# BSB-Board.net
KiCad netlist of a schematic drawn in EAGLE
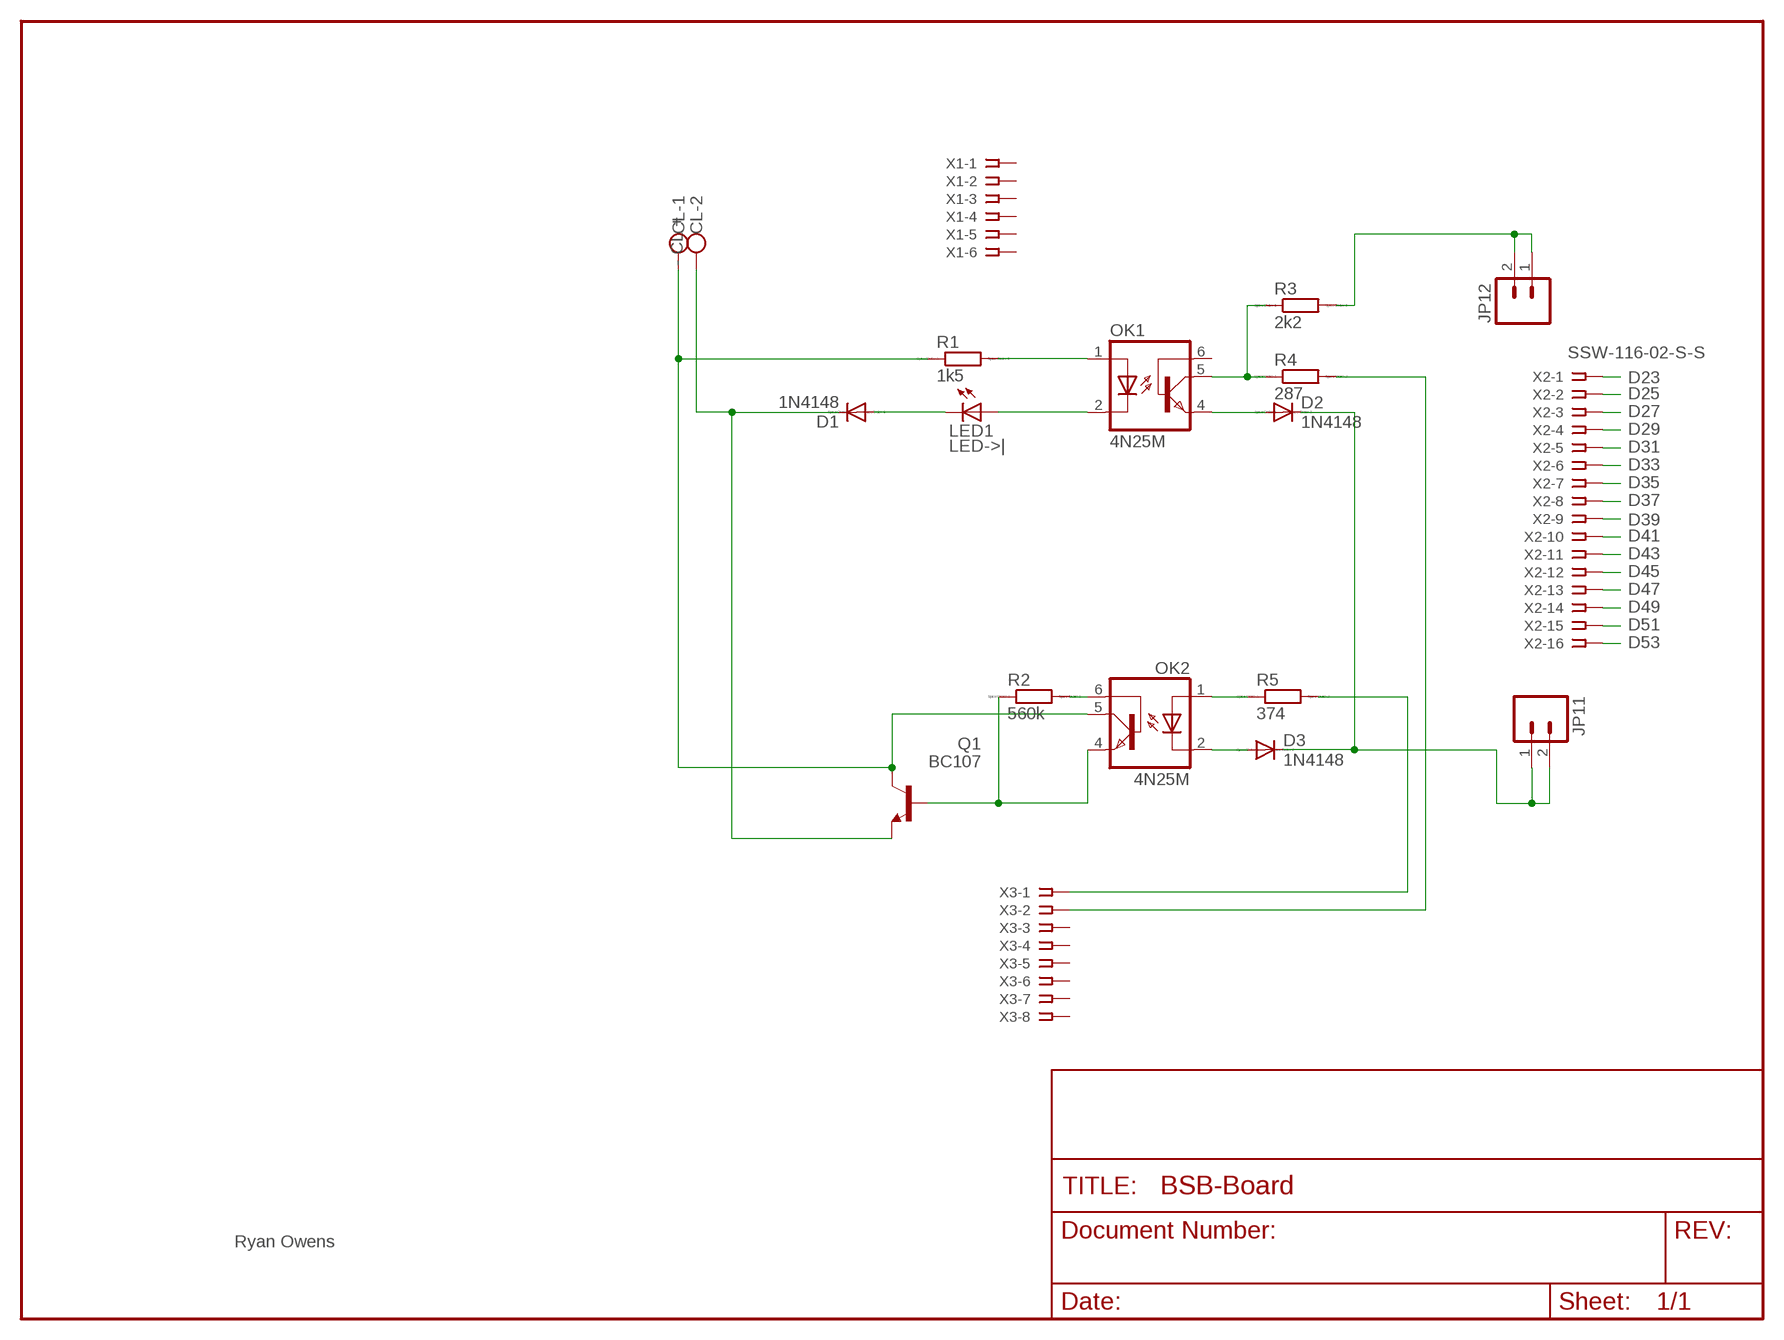
[diagram p0: schematic, sheet 1]

(export (version "E")
  (design (tool "Eeschema 10.0.6"))
  (components
    (comp (ref "CL")
      (value "- CL +")
      (footprint "eagle-import:W237-102")
      (fields (field (name "MPN") "237-102"))
      (libsource (lib "eagle-import") (part "W237-102"))
    )
    (comp (ref "D1")
      (value "1N4148")
      (footprint "eagle-import:DO35-7")
      (libsource (lib "eagle-import") (part "1N4148DO35-7"))
    )
    (comp (ref "D2")
      (value "1N4148")
      (footprint "eagle-import:DO35-7")
      (libsource (lib "eagle-import") (part "1N4148DO35-7"))
    )
    (comp (ref "D3")
      (value "1N4148")
      (footprint "eagle-import:DO35-7")
      (libsource (lib "eagle-import") (part "1N4148DO35-7"))
    )
    (comp (ref "JP11")
      (value "M02LOCK")
      (footprint "eagle-import:1X02_LOCK")
      (libsource (lib "eagle-import") (part "M02LOCK"))
    )
    (comp (ref "JP12")
      (value "M02LOCK")
      (footprint "eagle-import:1X02_LOCK")
      (libsource (lib "eagle-import") (part "M02LOCK"))
    )
    (comp (ref "LED1")
      (value "LED->|")
      (footprint "eagle-import:LED2X5")
      (libsource (lib "eagle-import") (part "LEDSQR2X5"))
    )
    (comp (ref "OK1")
      (value "4N25M")
      (footprint "eagle-import:DIL06")
      (fields (field (name "MPN") "4N25-M"))
      (libsource (lib "eagle-import") (part "4N?M25"))
    )
    (comp (ref "OK2")
      (value "4N25M")
      (footprint "eagle-import:DIL06")
      (fields (field (name "MPN") "4N25-M"))
      (libsource (lib "eagle-import") (part "4N?M25"))
    )
    (comp (ref "Q1")
      (value "BC107")
      (footprint "eagle-import:TO18")
      (libsource (lib "eagle-import") (part "BC107"))
    )
    (comp (ref "R1")
      (value "1k5")
      (footprint "eagle-import:0204_7")
      (libsource (lib "eagle-import") (part "R0204/7"))
    )
    (comp (ref "R2")
      (value "560k")
      (footprint "eagle-import:0207_10")
      (libsource (lib "eagle-import") (part "R0207/10"))
    )
    (comp (ref "R3")
      (value "2k2")
      (footprint "eagle-import:0204_7")
      (libsource (lib "eagle-import") (part "R0204/7"))
    )
    (comp (ref "R4")
      (value "287")
      (footprint "eagle-import:0204_7")
      (libsource (lib "eagle-import") (part "R0204/7"))
    )
    (comp (ref "R5")
      (value "374")
      (footprint "eagle-import:0204_7")
      (libsource (lib "eagle-import") (part "R0204/7"))
    )
    (comp (ref "X1")
      (value "SSW-106-02-S-S")
      (footprint "eagle-import:SSW-106-02-S-S")
      (libsource (lib "eagle-import") (part "SSW-106-02-S-S"))
    )
    (comp (ref "X2")
      (value "SSW-116-02-S-S")
      (footprint "eagle-import:SSW-116-02-S-S")
      (libsource (lib "eagle-import") (part "SSW-116-02-S-S"))
    )
    (comp (ref "X3")
      (value "SSW-108-02-S-S")
      (footprint "eagle-import:SSW-108-02-S-S")
      (libsource (lib "eagle-import") (part "SSW-108-02-S-S"))
    )
  )
  (nets
    (net (code "1") (name "/D23") (class "Default")
      (node (ref "X2") (pin "1") (pinfunction "1_1") (pintype "passive"))
    )
    (net (code "2") (name "/D25") (class "Default")
      (node (ref "X2") (pin "2") (pinfunction "1_2") (pintype "passive"))
    )
    (net (code "3") (name "/D27") (class "Default")
      (node (ref "X2") (pin "3") (pinfunction "1_3") (pintype "passive"))
    )
    (net (code "4") (name "/D29") (class "Default")
      (node (ref "X2") (pin "4") (pinfunction "1_4") (pintype "passive"))
    )
    (net (code "5") (name "/D31") (class "Default")
      (node (ref "X2") (pin "5") (pinfunction "1_5") (pintype "passive"))
    )
    (net (code "6") (name "/D33") (class "Default")
      (node (ref "X2") (pin "6") (pinfunction "1_6") (pintype "passive"))
    )
    (net (code "7") (name "/D35") (class "Default")
      (node (ref "X2") (pin "7") (pinfunction "1_7") (pintype "passive"))
    )
    (net (code "8") (name "/D37") (class "Default")
      (node (ref "X2") (pin "8") (pinfunction "1_8") (pintype "passive"))
    )
    (net (code "9") (name "/D39") (class "Default")
      (node (ref "X2") (pin "9") (pinfunction "1_9") (pintype "passive"))
    )
    (net (code "10") (name "/D41") (class "Default")
      (node (ref "X2") (pin "10") (pinfunction "1_10") (pintype "passive"))
    )
    (net (code "11") (name "/D43") (class "Default")
      (node (ref "X2") (pin "11") (pinfunction "1_11") (pintype "passive"))
    )
    (net (code "12") (name "/D45") (class "Default")
      (node (ref "X2") (pin "12") (pinfunction "1_12") (pintype "passive"))
    )
    (net (code "13") (name "/D47") (class "Default")
      (node (ref "X2") (pin "13") (pinfunction "1_13") (pintype "passive"))
    )
    (net (code "14") (name "/D49") (class "Default")
      (node (ref "X2") (pin "14") (pinfunction "1_14") (pintype "passive"))
    )
    (net (code "15") (name "/D51") (class "Default")
      (node (ref "X2") (pin "15") (pinfunction "1_15") (pintype "passive"))
    )
    (net (code "16") (name "/D53") (class "Default")
      (node (ref "X2") (pin "16") (pinfunction "1_16") (pintype "passive"))
    )
    (net (code "17") (name "Net-(CLA-KL)") (class "Default")
      (node (ref "CL") (pin "1") (pinfunction "KL_1") (pintype "passive"))
      (node (ref "OK2") (pin "5") (pinfunction "COL_5") (pintype "passive"))
      (node (ref "Q1") (pin "3") (pinfunction "C_3") (pintype "passive"))
      (node (ref "R1") (pin "1") (pinfunction "1_1") (pintype "passive"))
    )
    (net (code "18") (name "Net-(CLB-KL)") (class "Default")
      (node (ref "CL") (pin "2") (pinfunction "KL_2") (pintype "passive"))
      (node (ref "D1") (pin "C") (pinfunction "C_C") (pintype "passive"))
      (node (ref "Q1") (pin "1") (pinfunction "E_1") (pintype "passive"))
    )
    (net (code "19") (name "Net-(D2-PadC)") (class "Default")
      (node (ref "D2") (pin "C") (pinfunction "C_C") (pintype "passive"))
      (node (ref "D3") (pin "C") (pinfunction "C_C") (pintype "passive"))
      (node (ref "JP11") (pin "1") (pinfunction "1_1") (pintype "passive"))
      (node (ref "JP11") (pin "2") (pinfunction "2_2") (pintype "passive"))
    )
    (net (code "20") (name "Net-(JP12-Pad1)") (class "Default")
      (node (ref "JP12") (pin "1") (pinfunction "1_1") (pintype "passive"))
      (node (ref "JP12") (pin "2") (pinfunction "2_2") (pintype "passive"))
      (node (ref "R3") (pin "2") (pinfunction "2_2") (pintype "passive"))
    )
    (net (code "21") (name "Net-(LED1-C)") (class "Default")
      (node (ref "D1") (pin "A") (pinfunction "A_A") (pintype "passive"))
      (node (ref "LED1") (pin "K") (pinfunction "C_K") (pintype "passive"))
    )
    (net (code "22") (name "Net-(OK1-A)") (class "Default")
      (node (ref "OK1") (pin "1") (pinfunction "A_1") (pintype "passive"))
      (node (ref "R1") (pin "2") (pinfunction "2_2") (pintype "passive"))
    )
    (net (code "23") (name "Net-(OK1-C)") (class "Default")
      (node (ref "LED1") (pin "A") (pinfunction "A_A") (pintype "passive"))
      (node (ref "OK1") (pin "2") (pinfunction "C_2") (pintype "passive"))
    )
    (net (code "24") (name "Net-(OK1-COL)") (class "Default")
      (node (ref "OK1") (pin "5") (pinfunction "COL_5") (pintype "passive"))
      (node (ref "R3") (pin "1") (pinfunction "1_1") (pintype "passive"))
      (node (ref "R4") (pin "1") (pinfunction "1_1") (pintype "passive"))
    )
    (net (code "25") (name "Net-(OK1-EMI)") (class "Default")
      (node (ref "D2") (pin "A") (pinfunction "A_A") (pintype "passive"))
      (node (ref "OK1") (pin "4") (pinfunction "EMI_4") (pintype "passive"))
    )
    (net (code "26") (name "Net-(OK2-A)") (class "Default")
      (node (ref "OK2") (pin "1") (pinfunction "A_1") (pintype "passive"))
      (node (ref "R5") (pin "1") (pinfunction "1_1") (pintype "passive"))
    )
    (net (code "27") (name "Net-(OK2-BAS)") (class "Default")
      (node (ref "OK2") (pin "6") (pinfunction "BAS_6") (pintype "passive"))
      (node (ref "R2") (pin "2") (pinfunction "2_2") (pintype "passive"))
    )
    (net (code "28") (name "Net-(OK2-C)") (class "Default")
      (node (ref "D3") (pin "A") (pinfunction "A_A") (pintype "passive"))
      (node (ref "OK2") (pin "2") (pinfunction "C_2") (pintype "passive"))
    )
    (net (code "29") (name "Net-(OK2-EMI)") (class "Default")
      (node (ref "OK2") (pin "4") (pinfunction "EMI_4") (pintype "passive"))
      (node (ref "Q1") (pin "2") (pinfunction "B_2") (pintype "passive"))
      (node (ref "R2") (pin "1") (pinfunction "1_1") (pintype "passive"))
    )
    (net (code "30") (name "Net-(R5-Pad2)") (class "Default")
      (node (ref "R5") (pin "2") (pinfunction "2_2") (pintype "passive"))
      (node (ref "X3") (pin "1") (pinfunction "1_1") (pintype "passive"))
    )
    (net (code "31") (name "Net-(X3B-1)") (class "Default")
      (node (ref "R4") (pin "2") (pinfunction "2_2") (pintype "passive"))
      (node (ref "X3") (pin "2") (pinfunction "1_2") (pintype "passive"))
    )
    (net (code "32") (name "unconnected-(OK1-BAS-Pad6)") (class "Default")
      (node (ref "OK1") (pin "6") (pinfunction "BAS_6") (pintype "passive"))
    )
    (net (code "33") (name "unconnected-(X1-Pad1)") (class "Default")
      (node (ref "X1") (pin "1") (pinfunction "1_1") (pintype "passive"))
    )
    (net (code "34") (name "unconnected-(X1B-1-Pad2)") (class "Default")
      (node (ref "X1") (pin "2") (pinfunction "1_2") (pintype "passive"))
    )
    (net (code "35") (name "unconnected-(X1C-1-Pad3)") (class "Default")
      (node (ref "X1") (pin "3") (pinfunction "1_3") (pintype "passive"))
    )
    (net (code "36") (name "unconnected-(X1D-1-Pad4)") (class "Default")
      (node (ref "X1") (pin "4") (pinfunction "1_4") (pintype "passive"))
    )
    (net (code "37") (name "unconnected-(X1E-1-Pad5)") (class "Default")
      (node (ref "X1") (pin "5") (pinfunction "1_5") (pintype "passive"))
    )
    (net (code "38") (name "unconnected-(X1F-1-Pad6)") (class "Default")
      (node (ref "X1") (pin "6") (pinfunction "1_6") (pintype "passive"))
    )
    (net (code "39") (name "unconnected-(X3C-1-Pad3)") (class "Default")
      (node (ref "X3") (pin "3") (pinfunction "1_3") (pintype "passive"))
    )
    (net (code "40") (name "unconnected-(X3D-1-Pad4)") (class "Default")
      (node (ref "X3") (pin "4") (pinfunction "1_4") (pintype "passive"))
    )
    (net (code "41") (name "unconnected-(X3E-1-Pad5)") (class "Default")
      (node (ref "X3") (pin "5") (pinfunction "1_5") (pintype "passive"))
    )
    (net (code "42") (name "unconnected-(X3F-1-Pad6)") (class "Default")
      (node (ref "X3") (pin "6") (pinfunction "1_6") (pintype "passive"))
    )
    (net (code "43") (name "unconnected-(X3G-1-Pad7)") (class "Default")
      (node (ref "X3") (pin "7") (pinfunction "1_7") (pintype "passive"))
    )
    (net (code "44") (name "unconnected-(X3H-1-Pad8)") (class "Default")
      (node (ref "X3") (pin "8") (pinfunction "1_8") (pintype "passive"))
    )
  )
)
